# E-0056_TMC2130.net
KiCad netlist of a schematic drawn in Altium Designer
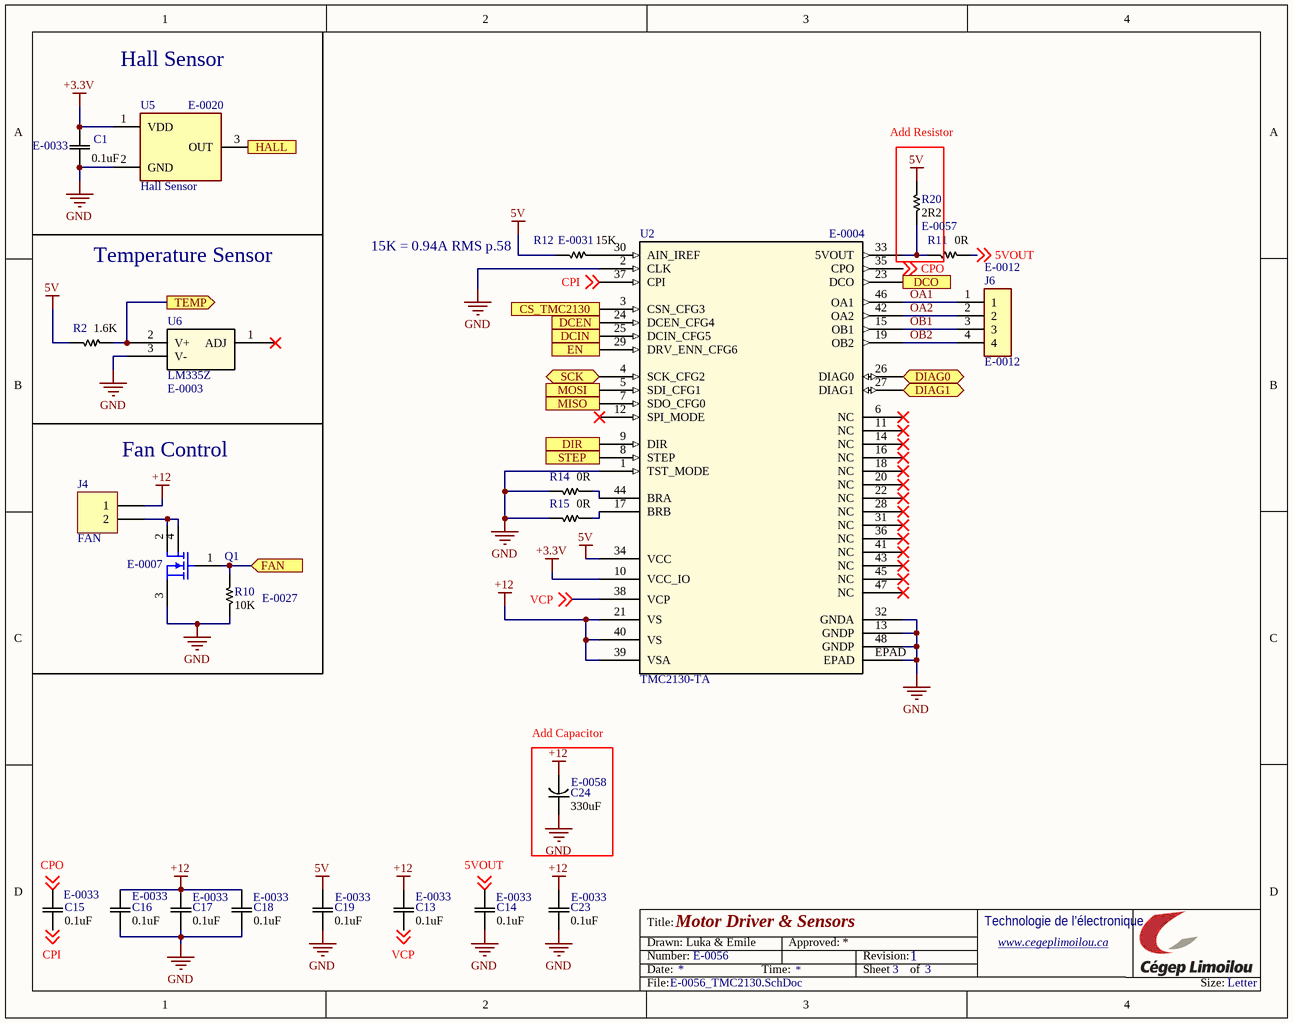
[diagram p0: E-0056_TMC2130.SchDoc]

(export (version "E")
  (design (tool "Eeschema 10.0.6"))
  (components
    (comp (ref "C1")
      (value "0.1uF")
      (footprint "0603")
      (description "0.1uF Capacitor 0603 SMD")
      (fields
        (field (name "MANUFACTURER_PART_NUMBER") "C0603C104Z3VACTU")
        (field (name "EXCEL NUMBER") "E-0033")
        (field (name "Comment") "E-0033")
        (field (name "COPYRIGHT") "Luka & Émile")
      )
      (libsource (lib "Motor Driver") (part "E-0033"))
    )
    (comp (ref "C13")
      (value "0.1uF")
      (footprint "0603")
      (description "0.1uF Capacitor 0603 SMD")
      (fields
        (field (name "MANUFACTURER_PART_NUMBER") "C0603C104Z3VACTU")
        (field (name "EXCEL NUMBER") "E-0033")
        (field (name "Comment") "E-0033")
        (field (name "COPYRIGHT") "Luka & Émile")
      )
      (libsource (lib "Motor Driver") (part "E-0033"))
    )
    (comp (ref "C14")
      (value "0.1uF")
      (footprint "0603")
      (description "0.1uF Capacitor 0603 SMD")
      (fields
        (field (name "MANUFACTURER_PART_NUMBER") "C0603C104Z3VACTU")
        (field (name "EXCEL NUMBER") "E-0033")
        (field (name "Comment") "E-0033")
        (field (name "COPYRIGHT") "Luka & Émile")
      )
      (libsource (lib "Motor Driver") (part "E-0033"))
    )
    (comp (ref "C15")
      (value "0.1uF")
      (footprint "0603")
      (description "0.1uF Capacitor 0603 SMD")
      (fields
        (field (name "MANUFACTURER_PART_NUMBER") "C0603C104Z3VACTU")
        (field (name "EXCEL NUMBER") "E-0033")
        (field (name "Comment") "E-0033")
        (field (name "COPYRIGHT") "Luka & Émile")
      )
      (libsource (lib "Motor Driver") (part "E-0033"))
    )
    (comp (ref "C16")
      (value "0.1uF")
      (footprint "0603")
      (description "0.1uF Capacitor 0603 SMD")
      (fields
        (field (name "MANUFACTURER_PART_NUMBER") "C0603C104Z3VACTU")
        (field (name "EXCEL NUMBER") "E-0033")
        (field (name "Comment") "E-0033")
        (field (name "COPYRIGHT") "Luka & Émile")
      )
      (libsource (lib "Motor Driver") (part "E-0033"))
    )
    (comp (ref "C17")
      (value "0.1uF")
      (footprint "0603")
      (description "0.1uF Capacitor 0603 SMD")
      (fields
        (field (name "MANUFACTURER_PART_NUMBER") "C0603C104Z3VACTU")
        (field (name "EXCEL NUMBER") "E-0033")
        (field (name "Comment") "E-0033")
        (field (name "COPYRIGHT") "Luka & Émile")
      )
      (libsource (lib "Motor Driver") (part "E-0033"))
    )
    (comp (ref "C18")
      (value "0.1uF")
      (footprint "0603")
      (description "0.1uF Capacitor 0603 SMD")
      (fields
        (field (name "MANUFACTURER_PART_NUMBER") "C0603C104Z3VACTU")
        (field (name "EXCEL NUMBER") "E-0033")
        (field (name "Comment") "E-0033")
        (field (name "COPYRIGHT") "Luka & Émile")
      )
      (libsource (lib "Motor Driver") (part "E-0033"))
    )
    (comp (ref "C19")
      (value "0.1uF")
      (footprint "0603")
      (description "0.1uF Capacitor 0603 SMD")
      (fields
        (field (name "MANUFACTURER_PART_NUMBER") "C0603C104Z3VACTU")
        (field (name "EXCEL NUMBER") "E-0033")
        (field (name "Comment") "E-0033")
        (field (name "COPYRIGHT") "Luka & Émile")
      )
      (libsource (lib "Motor Driver") (part "E-0033"))
    )
    (comp (ref "C23")
      (value "0.1uF")
      (footprint "0603")
      (description "0.1uF Capacitor 0603 SMD")
      (fields
        (field (name "MANUFACTURER_PART_NUMBER") "C0603C104Z3VACTU")
        (field (name "EXCEL NUMBER") "E-0033")
        (field (name "Comment") "E-0033")
        (field (name "COPYRIGHT") "Luka & Émile")
      )
      (libsource (lib "Motor Driver") (part "E-0033"))
    )
    (comp (ref "C24")
      (value "330uF")
      (footprint "0603")
      (description "330uF Capacitor TH")
      (fields
        (field (name "MANUFACTURER_PART_NUMBER") "C0603C475K9PACTU")
        (field (name "EXCEL NUMBER") "E-0058")
        (field (name "Comment") "Capacitor SMD")
        (field (name "COPYRIGHT") "Luka & Émile")
      )
      (libsource (lib "Motor Driver") (part "E-0058"))
    )
    (comp (ref "J4")
      (value "FAN")
      (footprint "HDR1X2")
      (description "Header, 2-Pin")
      (fields
        (field (name "MANUFACTURER_PART_NUMBER") "61300411121")
        (field (name "COPYRIGHT") "Luka & Émile")
      )
      (libsource (lib "Motor Driver") (part "E-0047"))
    )
    (comp (ref "J6")
      (value "E-0012")
      (footprint "JST 4POS 2.5mm 90°")
      (description "Connector JST 4POS")
      (fields
        (field (name "MANUFACTURER_PART_NUMBER") "S4B-XH-A(LF)(SN)")
        (field (name "EXCEL NUMBER") "E-0012")
        (field (name "COPYRIGHT") "Luka & Émile")
      )
      (libsource (lib "Motor Driver") (part "E-0012"))
    )
    (comp (ref "Q1")
      (value "E-0007")
      (footprint "SOT223_M")
      (description "55V 7A SOT223")
      (fields
        (field (name "EXCEL NUMBER") "E-0007")
        (field (name "MANUFACTURER_PART_NUMBER") "BUK9880-55A/CUX")
        (field (name "COPYRIGHT") "Luka & Émile")
      )
      (libsource (lib "Motor Driver") (part "E-0007"))
    )
    (comp (ref "R2")
      (value "1.6K")
      (footprint "0603")
      (description "1.6K Resistor 0603 SMD")
      (fields
        (field (name "MANUFACTURER_PART_NUMBER") "CRCW06031K60JNEA")
        (field (name "Comment") "E-0050")
        (field (name "COPYRIGHT") "Luka & Émile")
      )
      (libsource (lib "Motor Driver") (part "E-0050"))
    )
    (comp (ref "R10")
      (value "10K")
      (footprint "0603")
      (description "10K Resistor 0603 SMD")
      (fields
        (field (name "MANUFACTURER_PART_NUMBER") "RMCF0603JT10K0")
        (field (name "EXCEL NUMBER") "E-0027")
        (field (name "Comment") "Resistor 0603")
        (field (name "COPYRIGHT") "Luka & Émile")
      )
      (libsource (lib "Motor Driver") (part "E-0027"))
    )
    (comp (ref "R11")
      (value "0R")
      (footprint "0603")
      (description "Jumper 0603")
      (fields (field (name "Comment") "Jumper") (field (name "COPYRIGHT") "Luka & Émile"))
      (libsource (lib "Motor Driver") (part "Jumper"))
    )
    (comp (ref "R12")
      (value "15K")
      (footprint "0603")
      (description "15K Resistor 0603 SMD")
      (fields
        (field (name "MANUFACTURER_PART_NUMBER") "RMCF0603FG15K0")
        (field (name "EXCEL NUMBER") "E-0031")
        (field (name "Comment") "E-0031")
        (field (name "COPYRIGHT") "Luka & Émile")
      )
      (libsource (lib "Motor Driver") (part "E-0031"))
    )
    (comp (ref "R14")
      (value "0R")
      (footprint "0603")
      (description "Jumper 0603")
      (fields (field (name "Comment") "Jumper") (field (name "COPYRIGHT") "Luka & Émile"))
      (libsource (lib "Motor Driver") (part "Jumper"))
    )
    (comp (ref "R15")
      (value "0R")
      (footprint "0603")
      (description "Jumper 0603")
      (fields (field (name "Comment") "Jumper") (field (name "COPYRIGHT") "Luka & Émile"))
      (libsource (lib "Motor Driver") (part "Jumper"))
    )
    (comp (ref "R20")
      (value "2R2")
      (footprint "0603")
      (description "2R2 Resistor 0603 SMD")
      (fields
        (field (name "MANUFACTURER_PART_NUMBER") "CRCW06031K60JNEA")
        (field (name "EXCEL NUMBER") "E-0057")
        (field (name "Comment") "Resistor 0603")
        (field (name "COPYRIGHT") "Luka & Émile")
      )
      (libsource (lib "Motor Driver") (part "E-0057"))
    )
    (comp (ref "U2")
      (value "TMC2130-TA")
      (footprint "eTQFP48_9x9")
      (description "Motor Driver TMC2130-TA")
      (fields
        (field (name "MANUFACTURER_PART_NUMBER") "TMC2130-TA-T")
        (field (name "EXCEL NUMBER") "E-0004")
        (field (name "COPYRIGHT") "Luka & Émile")
      )
      (libsource (lib "Motor Driver") (part "E-0004"))
    )
    (comp (ref "U5")
      (value "Hall Sensor")
      (footprint "Footprint_Emile:AH372PB")
      (fields
        (field (name "MANUFACTURER_PART_NUMBER") "AH372-P-B")
        (field (name "EXCEL NUMBER") "E-0020")
        (field (name "COPYRIGHT") "Luka & Émile")
      )
      (libsource (lib "Motor Driver") (part "E-0020"))
    )
    (comp (ref "U6")
      (value "LM335Z")
      (footprint "TO92")
      (description "Temperature Sensor LM335Z")
      (fields (field (name "EXCEL NUMBER") "E-0003") (field (name "COPYRIGHT") "Luka & Émile"))
      (libsource (lib "Motor Driver") (part "E-0003"))
    )
  )
  (nets
    (net (code "1") (name "+3.3V") (class "Default")
      (node (ref "C1") (pin "2") (pinfunction "2_2") (pintype "passive"))
      (node (ref "U2") (pin "10") (pinfunction "VCC_IO_10") (pintype "power_in"))
      (node (ref "U5") (pin "1") (pinfunction "VDD_1") (pintype "passive"))
    )
    (net (code "2") (name "+12") (class "Default")
      (node (ref "C13") (pin "2") (pinfunction "2_2") (pintype "passive"))
      (node (ref "C16") (pin "2") (pinfunction "2_2") (pintype "passive"))
      (node (ref "C17") (pin "2") (pinfunction "2_2") (pintype "passive"))
      (node (ref "C18") (pin "2") (pinfunction "2_2") (pintype "passive"))
      (node (ref "C23") (pin "2") (pinfunction "2_2") (pintype "passive"))
      (node (ref "C24") (pin "2") (pinfunction "2_2") (pintype "passive"))
      (node (ref "J4") (pin "1") (pinfunction "1_1") (pintype "passive"))
      (node (ref "U2") (pin "21") (pinfunction "VS_21") (pintype "power_in"))
      (node (ref "U2") (pin "39") (pinfunction "VSA_39") (pintype "power_in"))
      (node (ref "U2") (pin "40") (pinfunction "VS_40") (pintype "power_in"))
    )
    (net (code "3") (name "/CS_TMC2130") (class "Default")
      (node (ref "U2") (pin "3") (pinfunction "CSN_CFG3_3") (pintype "input"))
    )
    (net (code "4") (name "/DCEN") (class "Default")
      (node (ref "U2") (pin "24") (pinfunction "DCEN_CFG4_24") (pintype "input"))
    )
    (net (code "5") (name "/DCIN") (class "Default")
      (node (ref "U2") (pin "25") (pinfunction "DCIN_CFG5_25") (pintype "input"))
    )
    (net (code "6") (name "/DCO") (class "Default")
      (node (ref "U2") (pin "23") (pinfunction "DCO_23") (pintype "output"))
    )
    (net (code "7") (name "/DIAG0") (class "Default")
      (node (ref "U2") (pin "26") (pinfunction "DIAG0_26") (pintype "bidirectional"))
    )
    (net (code "8") (name "/DIAG1") (class "Default")
      (node (ref "U2") (pin "27") (pinfunction "DIAG1_27") (pintype "bidirectional"))
    )
    (net (code "9") (name "/DIR") (class "Default")
      (node (ref "U2") (pin "9") (pinfunction "DIR_9") (pintype "input"))
    )
    (net (code "10") (name "/EN") (class "Default")
      (node (ref "U2") (pin "29") (pinfunction "DRV_ENN_CFG6_29") (pintype "input"))
    )
    (net (code "11") (name "/FAN") (class "Default")
      (node (ref "Q1") (pin "1") (pinfunction "G_1") (pintype "passive"))
      (node (ref "R10") (pin "2") (pinfunction "2_2") (pintype "passive"))
    )
    (net (code "12") (name "/HALL") (class "Default")
      (node (ref "U5") (pin "3") (pinfunction "OUT_3") (pintype "passive"))
    )
    (net (code "13") (name "/MISO") (class "Default")
      (node (ref "U2") (pin "7") (pinfunction "SDO_CFG0_7") (pintype "input"))
    )
    (net (code "14") (name "/MOSI") (class "Default")
      (node (ref "U2") (pin "5") (pinfunction "SDI_CFG1_5") (pintype "input"))
    )
    (net (code "15") (name "/OA1") (class "Default")
      (node (ref "J6") (pin "1") (pinfunction "1_1") (pintype "passive"))
      (node (ref "U2") (pin "46") (pinfunction "OA1_46") (pintype "output"))
    )
    (net (code "16") (name "/OA2") (class "Default")
      (node (ref "J6") (pin "2") (pinfunction "2_2") (pintype "passive"))
      (node (ref "U2") (pin "42") (pinfunction "OA2_42") (pintype "output"))
    )
    (net (code "17") (name "/OB1") (class "Default")
      (node (ref "J6") (pin "3") (pinfunction "3_3") (pintype "passive"))
      (node (ref "U2") (pin "15") (pinfunction "OB1_15") (pintype "output"))
    )
    (net (code "18") (name "/OB2") (class "Default")
      (node (ref "J6") (pin "4") (pinfunction "4_4") (pintype "passive"))
      (node (ref "U2") (pin "19") (pinfunction "OB2_19") (pintype "output"))
    )
    (net (code "19") (name "/SCK") (class "Default")
      (node (ref "U2") (pin "4") (pinfunction "SCK_CFG2_4") (pintype "input"))
    )
    (net (code "20") (name "/STEP") (class "Default")
      (node (ref "U2") (pin "8") (pinfunction "STEP_8") (pintype "input"))
    )
    (net (code "21") (name "/TEMP") (class "Default")
      (node (ref "R2") (pin "2") (pinfunction "2_2") (pintype "passive"))
      (node (ref "U6") (pin "2") (pinfunction "V+_2") (pintype "power_in"))
    )
    (net (code "22") (name "5V") (class "Default")
      (node (ref "C19") (pin "2") (pinfunction "2_2") (pintype "passive"))
      (node (ref "R12") (pin "1") (pinfunction "1_1") (pintype "passive"))
      (node (ref "R2") (pin "1") (pinfunction "1_1") (pintype "passive"))
      (node (ref "R20") (pin "2") (pinfunction "2_2") (pintype "passive"))
      (node (ref "U2") (pin "34") (pinfunction "VCC_34") (pintype "power_in"))
    )
    (net (code "23") (name "5VOUT") (class "Default")
      (node (ref "C14") (pin "2") (pinfunction "2_2") (pintype "passive"))
      (node (ref "R11") (pin "2") (pinfunction "2_2") (pintype "passive"))
    )
    (net (code "24") (name "CPI") (class "Default")
      (node (ref "C15") (pin "1") (pinfunction "1_1") (pintype "passive"))
      (node (ref "U2") (pin "37") (pinfunction "CPI_37") (pintype "input"))
    )
    (net (code "25") (name "CPO") (class "Default")
      (node (ref "C15") (pin "2") (pinfunction "2_2") (pintype "passive"))
      (node (ref "U2") (pin "35") (pinfunction "CPO_35") (pintype "output"))
    )
    (net (code "26") (name "GND") (class "Default")
      (node (ref "C1") (pin "1") (pinfunction "1_1") (pintype "passive"))
      (node (ref "C14") (pin "1") (pinfunction "1_1") (pintype "passive"))
      (node (ref "C16") (pin "1") (pinfunction "1_1") (pintype "passive"))
      (node (ref "C17") (pin "1") (pinfunction "1_1") (pintype "passive"))
      (node (ref "C18") (pin "1") (pinfunction "1_1") (pintype "passive"))
      (node (ref "C19") (pin "1") (pinfunction "1_1") (pintype "passive"))
      (node (ref "C23") (pin "1") (pinfunction "1_1") (pintype "passive"))
      (node (ref "C24") (pin "1") (pinfunction "1_1") (pintype "passive"))
      (node (ref "Q1") (pin "3") (pinfunction "S_3") (pintype "passive"))
      (node (ref "R10") (pin "1") (pinfunction "1_1") (pintype "passive"))
      (node (ref "R14") (pin "1") (pinfunction "1_1") (pintype "passive"))
      (node (ref "R15") (pin "1") (pinfunction "1_1") (pintype "passive"))
      (node (ref "U2") (pin "1") (pinfunction "TST_MODE_1") (pintype "input"))
      (node (ref "U2") (pin "13") (pinfunction "GNDP_13") (pintype "power_in"))
      (node (ref "U2") (pin "2") (pinfunction "CLK_2") (pintype "input"))
      (node (ref "U2") (pin "32") (pinfunction "GNDA_32") (pintype "power_in"))
      (node (ref "U2") (pin "48") (pinfunction "GNDP_48") (pintype "power_in"))
      (node (ref "U2") (pin "EPAD") (pinfunction "EPAD_EPAD") (pintype "passive"))
      (node (ref "U5") (pin "2") (pinfunction "GND_2") (pintype "passive"))
      (node (ref "U6") (pin "3") (pinfunction "V-_3") (pintype "power_in"))
    )
    (net (code "27") (name "Net-(J4-Pad2)") (class "Default")
      (node (ref "J4") (pin "2") (pinfunction "2_2") (pintype "passive"))
      (node (ref "Q1") (pin "2") (pinfunction "D_2") (pintype "passive"))
      (node (ref "Q1") (pin "4") (pinfunction "D_4") (pintype "passive"))
    )
    (net (code "28") (name "Net-(U2-5VOUT)") (class "Default")
      (node (ref "R11") (pin "1") (pinfunction "1_1") (pintype "passive"))
      (node (ref "R20") (pin "1") (pinfunction "1_1") (pintype "passive"))
      (node (ref "U2") (pin "33") (pinfunction "5VOUT_33") (pintype "output"))
    )
    (net (code "29") (name "Net-(U2-AIN_IREF)") (class "Default")
      (node (ref "R12") (pin "2") (pinfunction "2_2") (pintype "passive"))
      (node (ref "U2") (pin "30") (pinfunction "AIN_IREF_30") (pintype "input"))
    )
    (net (code "30") (name "Net-(U2-BRA)") (class "Default")
      (node (ref "R14") (pin "2") (pinfunction "2_2") (pintype "passive"))
      (node (ref "U2") (pin "44") (pinfunction "BRA_44") (pintype "passive"))
    )
    (net (code "31") (name "Net-(U2-BRB)") (class "Default")
      (node (ref "R15") (pin "2") (pinfunction "2_2") (pintype "passive"))
      (node (ref "U2") (pin "17") (pinfunction "BRB_17") (pintype "passive"))
    )
    (net (code "32") (name "VCP") (class "Default")
      (node (ref "C13") (pin "1") (pinfunction "1_1") (pintype "passive"))
      (node (ref "U2") (pin "38") (pinfunction "VCP_38") (pintype "power_in"))
    )
    (net (code "33") (name "unconnected-(U2-NC-Pad6)") (class "Default")
      (node (ref "U2") (pin "6") (pinfunction "NC_6") (pintype "passive+no_connect"))
    )
    (net (code "34") (name "unconnected-(U2-NC-Pad11)") (class "Default")
      (node (ref "U2") (pin "11") (pinfunction "NC_11") (pintype "passive+no_connect"))
    )
    (net (code "35") (name "unconnected-(U2-NC-Pad14)") (class "Default")
      (node (ref "U2") (pin "14") (pinfunction "NC_14") (pintype "passive+no_connect"))
    )
    (net (code "36") (name "unconnected-(U2-NC-Pad16)") (class "Default")
      (node (ref "U2") (pin "16") (pinfunction "NC_16") (pintype "passive+no_connect"))
    )
    (net (code "37") (name "unconnected-(U2-NC-Pad18)") (class "Default")
      (node (ref "U2") (pin "18") (pinfunction "NC_18") (pintype "passive+no_connect"))
    )
    (net (code "38") (name "unconnected-(U2-NC-Pad20)") (class "Default")
      (node (ref "U2") (pin "20") (pinfunction "NC_20") (pintype "passive+no_connect"))
    )
    (net (code "39") (name "unconnected-(U2-NC-Pad22)") (class "Default")
      (node (ref "U2") (pin "22") (pinfunction "NC_22") (pintype "passive+no_connect"))
    )
    (net (code "40") (name "unconnected-(U2-NC-Pad28)") (class "Default")
      (node (ref "U2") (pin "28") (pinfunction "NC_28") (pintype "passive+no_connect"))
    )
    (net (code "41") (name "unconnected-(U2-NC-Pad31)") (class "Default")
      (node (ref "U2") (pin "31") (pinfunction "NC_31") (pintype "passive+no_connect"))
    )
    (net (code "42") (name "unconnected-(U2-NC-Pad36)") (class "Default")
      (node (ref "U2") (pin "36") (pinfunction "NC_36") (pintype "passive+no_connect"))
    )
    (net (code "43") (name "unconnected-(U2-NC-Pad41)") (class "Default")
      (node (ref "U2") (pin "41") (pinfunction "NC_41") (pintype "passive+no_connect"))
    )
    (net (code "44") (name "unconnected-(U2-NC-Pad43)") (class "Default")
      (node (ref "U2") (pin "43") (pinfunction "NC_43") (pintype "passive+no_connect"))
    )
    (net (code "45") (name "unconnected-(U2-NC-Pad45)") (class "Default")
      (node (ref "U2") (pin "45") (pinfunction "NC_45") (pintype "passive+no_connect"))
    )
    (net (code "46") (name "unconnected-(U2-NC-Pad47)") (class "Default")
      (node (ref "U2") (pin "47") (pinfunction "NC_47") (pintype "passive+no_connect"))
    )
    (net (code "47") (name "unconnected-(U2-SPI_MODE-Pad12)") (class "Default")
      (node (ref "U2") (pin "12") (pinfunction "SPI_MODE_12") (pintype "input+no_connect"))
    )
    (net (code "48") (name "unconnected-(U6-ADJ-Pad1)") (class "Default")
      (node (ref "U6") (pin "1") (pinfunction "ADJ_1") (pintype "passive+no_connect"))
    )
  )
)
